# CH32V005F6P6.net
KiCad netlist of a schematic drawn in Altium Designer
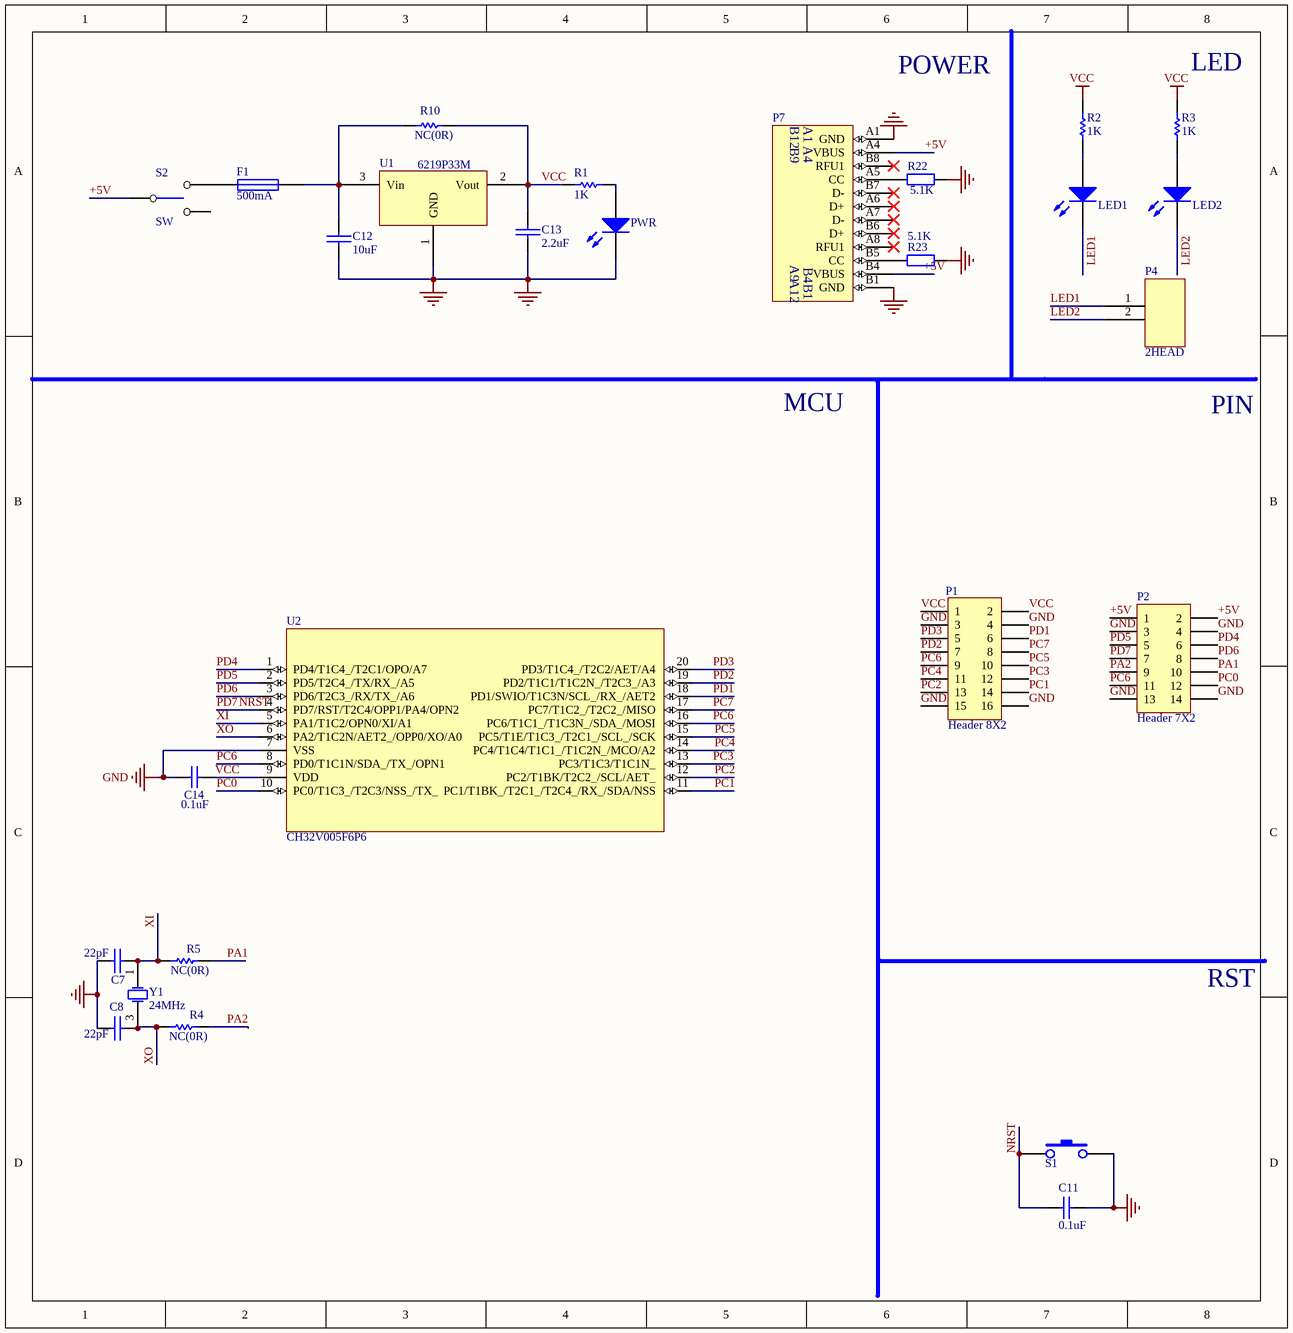
[diagram p0: CH32V005F6P6.SchDoc]

(export (version "E")
  (design (tool "Eeschema 10.0.6"))
  (components
    (comp (ref "C7")
      (value "22pF")
      (footprint "0402_C")
      (description "Capacitor")
      (libsource (lib "*") (part "CAP"))
    )
    (comp (ref "C8")
      (value "22pF")
      (footprint "0402_C")
      (description "Capacitor")
      (libsource (lib "*") (part "CAP"))
    )
    (comp (ref "C11")
      (value "0.1uF")
      (footprint "0603_C")
      (description "Capacitor")
      (fields (field (name "PUBLISHER") "Altium Limited"))
      (libsource (lib "*") (part "Cap"))
    )
    (comp (ref "C12")
      (value "10uF")
      (footprint "0603_C")
      (description "Capacitor")
      (libsource (lib "wch_sch_others") (part "CAP"))
    )
    (comp (ref "C13")
      (value "2.2uF")
      (footprint "0402_C")
      (description "Capacitor")
      (libsource (lib "wch_sch_others") (part "CAP"))
    )
    (comp (ref "C14")
      (value "0.1uF")
      (footprint "0603_C")
      (description "Capacitor")
      (fields (field (name "PUBLISHER") "Altium Limited"))
      (libsource (lib "*") (part "Cap"))
    )
    (comp (ref "F1")
      (value "500mA")
      (footprint "0603")
      (description "Fuse")
      (libsource (lib "*") (part "FUSE1"))
    )
    (comp (ref "LED1")
      (value "LED1   blue")
      (footprint "0603+")
      (description "Typical INFRARED GaAs LED")
      (fields (field (name "PUBLISHER") "Altium Limited"))
      (libsource (lib "*") (part "LED0"))
    )
    (comp (ref "LED2")
      (value "LED2  blue")
      (footprint "0603+")
      (description "Typical INFRARED GaAs LED")
      (fields (field (name "PUBLISHER") "Altium Limited"))
      (libsource (lib "*") (part "LED0"))
    )
    (comp (ref "P1")
      (value "Header 8X2")
      (footprint "HDR2X8")
      (description "Header, 8-Pin, Dual row")
      (fields (field (name "PUBLISHER") "Altium Limited"))
      (libsource (lib "Miscellaneous Connectors") (part "Header 8X2"))
    )
    (comp (ref "P2")
      (value "Header 7X2")
      (footprint "HDR2X7")
      (description "Header, 7-Pin, Dual row")
      (fields (field (name "PUBLISHER") "Altium Limited"))
      (libsource (lib "Miscellaneous Connectors") (part "Header 7X2"))
    )
    (comp (ref "P4") (value "2HEAD") (footprint "SIP2-2.54mm") (libsource (lib "*") (part "2HEAD")))
    (comp (ref "P7")
      (value "TYPE-C")
      (footprint "TYPE-C-Receptacle-2.0")
      (libsource (lib "*") (part "TYPE-C1"))
    )
    (comp (ref "PWR")
      (value "POWER  red")
      (footprint "0603+")
      (description "Typical INFRARED GaAs LED")
      (fields (field (name "PUBLISHER") "Altium Limited"))
      (libsource (lib "") (part "LED0_1"))
    )
    (comp (ref "R1")
      (value "1K")
      (footprint "0402")
      (description "Semiconductor Resistor")
      (fields (field (name "PUBLISHER") "Altium Limited"))
      (libsource (lib "*") (part "Res Semi"))
    )
    (comp (ref "R2")
      (value "1K")
      (footprint "0402")
      (description "Semiconductor Resistor")
      (fields (field (name "PUBLISHER") "Altium Limited"))
      (libsource (lib "*") (part "Res Semi"))
    )
    (comp (ref "R3")
      (value "1K")
      (footprint "0402")
      (description "Semiconductor Resistor")
      (fields (field (name "PUBLISHER") "Altium Limited"))
      (libsource (lib "*") (part "Res Semi"))
    )
    (comp (ref "R4")
      (value "NC(0R)")
      (footprint "0402")
      (description "Semiconductor Resistor")
      (fields (field (name "Comment") "0R") (field (name "PUBLISHER") "Altium Limited"))
      (libsource (lib "*") (part "Res Semi"))
    )
    (comp (ref "R5")
      (value "NC(0R)")
      (footprint "0402")
      (description "Semiconductor Resistor")
      (fields (field (name "Comment") "0R") (field (name "PUBLISHER") "Altium Limited"))
      (libsource (lib "*") (part "Res Semi"))
    )
    (comp (ref "R10")
      (value "NC(0R)")
      (footprint "0402")
      (description "Semiconductor Resistor")
      (fields (field (name "Comment") "0R") (field (name "PUBLISHER") "Altium Limited"))
      (libsource (lib "*") (part "Res Semi"))
    )
    (comp (ref "R22")
      (value "5.1K")
      (footprint "0402")
      (description "Resistor")
      (libsource (lib "Miscellaneous Devices") (part "Res2"))
    )
    (comp (ref "R23")
      (value "5.1K")
      (footprint "0402")
      (description "Resistor")
      (libsource (lib "Miscellaneous Devices") (part "Res2"))
    )
    (comp (ref "S1") (value "NRST") (footprint "SMD_6.1x3.65x2.5mm-KEY") (libsource (lib "*") (part "KEY")))
    (comp (ref "S2") (value "SW") (footprint "SW1") (libsource (lib "*") (part "SW")))
    (comp (ref "U1")
      (value "6219P33M")
      (footprint "SOT-23")
      (libsource (lib "wch_sch_others") (part "6219P33M"))
    )
    (comp (ref "U2")
      (value "CH32V005F6P6")
      (footprint "TSSOP20")
      (description "RISC-V MCU, 48MHz, ADC/OPA/2*UART/I2C/SPI")
      (libsource (lib "DHXXXSCH") (part "CH32V005F6P6"))
    )
    (comp (ref "Y1")
      (value "24MHz")
      (footprint "XT3225")
      (description "Crystal Oscillator")
      (fields (field (name "PUBLISHER") "Altium Limited"))
      (libsource (lib "*") (part "XTAL"))
    )
  )
  (nets
    (net (code "1") (name "/+5V") (class "Default")
      (node (ref "P2") (pin "1") (pinfunction "1_1") (pintype "passive"))
      (node (ref "P2") (pin "2") (pinfunction "2_2") (pintype "passive"))
      (node (ref "P7") (pin "A4") (pinfunction "VBUS_A4") (pintype "bidirectional"))
      (node (ref "P7") (pin "B4") (pinfunction "VBUS_B4") (pintype "bidirectional"))
      (node (ref "S2") (pin "1") (pinfunction "1_1") (pintype "passive"))
    )
    (net (code "2") (name "/LED1") (class "Default")
      (node (ref "LED1") (pin "2") (pinfunction "K_2") (pintype "passive"))
      (node (ref "P4") (pin "1") (pintype "passive"))
    )
    (net (code "3") (name "/LED2") (class "Default")
      (node (ref "LED2") (pin "2") (pinfunction "K_2") (pintype "passive"))
      (node (ref "P4") (pin "2") (pintype "passive"))
    )
    (net (code "4") (name "/NRST") (class "Default")
      (node (ref "C11") (pin "2") (pinfunction "2_2") (pintype "passive"))
      (node (ref "P2") (pin "7") (pinfunction "7_7") (pintype "passive"))
      (node (ref "S1") (pin "1") (pinfunction "1_1") (pintype "passive"))
      (node (ref "U2") (pin "4") (pinfunction "PD7/RST/T2C4/OPP1/PA4/OPN2_4") (pintype "bidirectional"))
    )
    (net (code "5") (name "/PA1") (class "Default")
      (node (ref "P2") (pin "10") (pinfunction "10_10") (pintype "passive"))
      (node (ref "R5") (pin "2") (pinfunction "2_2") (pintype "passive"))
    )
    (net (code "6") (name "/PA2") (class "Default")
      (node (ref "P2") (pin "9") (pinfunction "9_9") (pintype "passive"))
      (node (ref "R4") (pin "2") (pinfunction "2_2") (pintype "passive"))
    )
    (net (code "7") (name "/PC0") (class "Default")
      (node (ref "P2") (pin "12") (pinfunction "12_12") (pintype "passive"))
      (node (ref "U2") (pin "10") (pinfunction "PC0/T1C3_/T2C3/NSS_/TX__10") (pintype "bidirectional"))
    )
    (net (code "8") (name "/PC1") (class "Default")
      (node (ref "P1") (pin "14") (pinfunction "14_14") (pintype "passive"))
      (node (ref "U2") (pin "11") (pinfunction "PC1/T1BK_/T2C1_/T2C4_/RX_/SDA/NSS_11") (pintype "bidirectional"))
    )
    (net (code "9") (name "/PC2") (class "Default")
      (node (ref "P1") (pin "13") (pinfunction "13_13") (pintype "passive"))
      (node (ref "U2") (pin "12") (pinfunction "PC2/T1BK/T2C2_/SCL/AET__12") (pintype "bidirectional"))
    )
    (net (code "10") (name "/PC3") (class "Default")
      (node (ref "P1") (pin "12") (pinfunction "12_12") (pintype "passive"))
      (node (ref "U2") (pin "13") (pinfunction "PC3/T1C3/T1C1N__13") (pintype "bidirectional"))
    )
    (net (code "11") (name "/PC4") (class "Default")
      (node (ref "P1") (pin "11") (pinfunction "11_11") (pintype "passive"))
      (node (ref "U2") (pin "14") (pinfunction "PC4/T1C4/T1C1_/T1C2N_/MCO/A2_14") (pintype "bidirectional"))
    )
    (net (code "12") (name "/PC5") (class "Default")
      (node (ref "P1") (pin "10") (pinfunction "10_10") (pintype "passive"))
      (node (ref "U2") (pin "15") (pinfunction "PC5/T1E/T1C3_/T2C1_/SCL_/SCK_15") (pintype "bidirectional"))
    )
    (net (code "13") (name "/PC6") (class "Default")
      (node (ref "P1") (pin "9") (pinfunction "9_9") (pintype "passive"))
      (node (ref "P2") (pin "11") (pinfunction "11_11") (pintype "passive"))
      (node (ref "U2") (pin "16") (pinfunction "PC6/T1C1_/T1C3N_/SDA_/MOSI_16") (pintype "bidirectional"))
      (node (ref "U2") (pin "8") (pinfunction "PD0/T1C1N/SDA_/TX_/OPN1_8") (pintype "bidirectional"))
    )
    (net (code "14") (name "/PC7") (class "Default")
      (node (ref "P1") (pin "8") (pinfunction "8_8") (pintype "passive"))
      (node (ref "U2") (pin "17") (pinfunction "PC7/T1C2_/T2C2_/MISO_17") (pintype "bidirectional"))
    )
    (net (code "15") (name "/PD1") (class "Default")
      (node (ref "P1") (pin "6") (pinfunction "6_6") (pintype "passive"))
      (node (ref "U2") (pin "18") (pinfunction "PD1/SWIO/T1C3N/SCL_/RX_/AET2_18") (pintype "bidirectional"))
    )
    (net (code "16") (name "/PD2") (class "Default")
      (node (ref "P1") (pin "7") (pinfunction "7_7") (pintype "passive"))
      (node (ref "U2") (pin "19") (pinfunction "PD2/T1C1/T1C2N_/T2C3_/A3_19") (pintype "bidirectional"))
    )
    (net (code "17") (name "/PD3") (class "Default")
      (node (ref "P1") (pin "5") (pinfunction "5_5") (pintype "passive"))
      (node (ref "U2") (pin "20") (pinfunction "PD3/T1C4_/T2C2/AET/A4_20") (pintype "bidirectional"))
    )
    (net (code "18") (name "/PD4") (class "Default")
      (node (ref "P2") (pin "6") (pinfunction "6_6") (pintype "passive"))
      (node (ref "U2") (pin "1") (pinfunction "PD4/T1C4_/T2C1/OPO/A7_1") (pintype "bidirectional"))
    )
    (net (code "19") (name "/PD5") (class "Default")
      (node (ref "P2") (pin "5") (pinfunction "5_5") (pintype "passive"))
      (node (ref "U2") (pin "2") (pinfunction "PD5/T2C4_/TX/RX_/A5_2") (pintype "bidirectional"))
    )
    (net (code "20") (name "/PD6") (class "Default")
      (node (ref "P2") (pin "8") (pinfunction "8_8") (pintype "passive"))
      (node (ref "U2") (pin "3") (pinfunction "PD6/T2C3_/RX/TX_/A6_3") (pintype "bidirectional"))
    )
    (net (code "21") (name "/XI") (class "Default")
      (node (ref "C7") (pin "2") (pinfunction "2_2") (pintype "passive"))
      (node (ref "R5") (pin "1") (pinfunction "1_1") (pintype "passive"))
      (node (ref "U2") (pin "5") (pinfunction "PA1/T1C2/OPN0/XI/A1_5") (pintype "bidirectional"))
      (node (ref "Y1") (pin "1") (pinfunction "OSC1_1") (pintype "passive"))
    )
    (net (code "22") (name "/XO") (class "Default")
      (node (ref "C8") (pin "2") (pinfunction "2_2") (pintype "passive"))
      (node (ref "R4") (pin "1") (pinfunction "1_1") (pintype "passive"))
      (node (ref "U2") (pin "6") (pinfunction "PA2/T1C2N/AET2_/OPP0/XO/A0_6") (pintype "bidirectional"))
      (node (ref "Y1") (pin "3") (pinfunction "OSC2_3") (pintype "passive"))
    )
    (net (code "23") (name "GND") (class "Default")
      (node (ref "C11") (pin "1") (pinfunction "1_1") (pintype "passive"))
      (node (ref "C12") (pin "2") (pinfunction "2_2") (pintype "passive"))
      (node (ref "C13") (pin "1") (pinfunction "1_1") (pintype "passive"))
      (node (ref "C14") (pin "2") (pinfunction "2_2") (pintype "passive"))
      (node (ref "C7") (pin "1") (pinfunction "1_1") (pintype "passive"))
      (node (ref "C8") (pin "1") (pinfunction "1_1") (pintype "passive"))
      (node (ref "P1") (pin "15") (pinfunction "15_15") (pintype "passive"))
      (node (ref "P1") (pin "16") (pinfunction "16_16") (pintype "passive"))
      (node (ref "P1") (pin "3") (pinfunction "3_3") (pintype "passive"))
      (node (ref "P1") (pin "4") (pinfunction "4_4") (pintype "passive"))
      (node (ref "P2") (pin "13") (pinfunction "13_13") (pintype "passive"))
      (node (ref "P2") (pin "14") (pinfunction "14_14") (pintype "passive"))
      (node (ref "P2") (pin "3") (pinfunction "3_3") (pintype "passive"))
      (node (ref "P2") (pin "4") (pinfunction "4_4") (pintype "passive"))
      (node (ref "P7") (pin "A1") (pinfunction "GND_A1") (pintype "bidirectional"))
      (node (ref "P7") (pin "B1") (pinfunction "GND_B1") (pintype "bidirectional"))
      (node (ref "PWR") (pin "2") (pinfunction "K_2") (pintype "passive"))
      (node (ref "R22") (pin "2") (pinfunction "2_2") (pintype "passive"))
      (node (ref "R23") (pin "2") (pinfunction "2_2") (pintype "passive"))
      (node (ref "S1") (pin "2") (pinfunction "2_2") (pintype "passive"))
      (node (ref "U1") (pin "1") (pinfunction "GND_1") (pintype "passive"))
      (node (ref "U2") (pin "7") (pinfunction "VSS_7") (pintype "power_in"))
    )
    (net (code "24") (name "Net-(F1-Pad1)") (class "Default")
      (node (ref "F1") (pin "1") (pinfunction "1_1") (pintype "passive"))
      (node (ref "S2") (pin "3") (pinfunction "3_3") (pintype "passive"))
    )
    (net (code "25") (name "Net-(LED1-A)") (class "Default")
      (node (ref "LED1") (pin "1") (pinfunction "A_1") (pintype "passive"))
      (node (ref "R2") (pin "2") (pinfunction "2_2") (pintype "passive"))
    )
    (net (code "26") (name "Net-(LED2-A)") (class "Default")
      (node (ref "LED2") (pin "1") (pinfunction "A_1") (pintype "passive"))
      (node (ref "R3") (pin "2") (pinfunction "2_2") (pintype "passive"))
    )
    (net (code "27") (name "Net-(P7-CC-PadA5)") (class "Default")
      (node (ref "P7") (pin "A5") (pinfunction "CC_A5") (pintype "bidirectional"))
      (node (ref "R22") (pin "1") (pinfunction "1_1") (pintype "passive"))
    )
    (net (code "28") (name "Net-(P7-CC-PadB5)") (class "Default")
      (node (ref "P7") (pin "B5") (pinfunction "CC_B5") (pintype "bidirectional"))
      (node (ref "R23") (pin "1") (pinfunction "1_1") (pintype "passive"))
    )
    (net (code "29") (name "Net-(PWR-A)") (class "Default")
      (node (ref "PWR") (pin "1") (pinfunction "A_1") (pintype "passive"))
      (node (ref "R1") (pin "1") (pinfunction "1_1") (pintype "passive"))
    )
    (net (code "30") (name "Net-(U1-Vin)") (class "Default")
      (node (ref "C12") (pin "1") (pinfunction "1_1") (pintype "passive"))
      (node (ref "F1") (pin "2") (pinfunction "2_2") (pintype "passive"))
      (node (ref "R10") (pin "1") (pinfunction "1_1") (pintype "passive"))
      (node (ref "U1") (pin "3") (pinfunction "Vin_3") (pintype "passive"))
    )
    (net (code "31") (name "VCC") (class "Default")
      (node (ref "C13") (pin "2") (pinfunction "2_2") (pintype "passive"))
      (node (ref "C14") (pin "1") (pinfunction "1_1") (pintype "passive"))
      (node (ref "P1") (pin "1") (pinfunction "1_1") (pintype "passive"))
      (node (ref "P1") (pin "2") (pinfunction "2_2") (pintype "passive"))
      (node (ref "R1") (pin "2") (pinfunction "2_2") (pintype "passive"))
      (node (ref "R10") (pin "2") (pinfunction "2_2") (pintype "passive"))
      (node (ref "R2") (pin "1") (pinfunction "1_1") (pintype "passive"))
      (node (ref "R3") (pin "1") (pinfunction "1_1") (pintype "passive"))
      (node (ref "U1") (pin "2") (pinfunction "Vout_2") (pintype "passive"))
      (node (ref "U2") (pin "9") (pinfunction "VDD_9") (pintype "power_in"))
    )
    (net (code "32") (name "unconnected-(P7-D+-PadA6)") (class "Default")
      (node (ref "P7") (pin "A6") (pinfunction "D+_A6") (pintype "bidirectional+no_connect"))
    )
    (net (code "33") (name "unconnected-(P7-D+-PadB6)") (class "Default")
      (node (ref "P7") (pin "B6") (pinfunction "D+_B6") (pintype "bidirectional+no_connect"))
    )
    (net (code "34") (name "unconnected-(P7-D--PadA7)") (class "Default")
      (node (ref "P7") (pin "A7") (pinfunction "D-_A7") (pintype "bidirectional+no_connect"))
    )
    (net (code "35") (name "unconnected-(P7-D--PadB7)") (class "Default")
      (node (ref "P7") (pin "B7") (pinfunction "D-_B7") (pintype "bidirectional+no_connect"))
    )
    (net (code "36") (name "unconnected-(P7-RFU1-PadA8)") (class "Default")
      (node (ref "P7") (pin "A8") (pinfunction "RFU1_A8") (pintype "bidirectional+no_connect"))
    )
    (net (code "37") (name "unconnected-(P7-RFU1-PadB8)") (class "Default")
      (node (ref "P7") (pin "B8") (pinfunction "RFU1_B8") (pintype "bidirectional+no_connect"))
    )
    (net (code "38") (name "unconnected-(S2-Pad2)") (class "Default")
      (node (ref "S2") (pin "2") (pinfunction "2_2") (pintype "passive"))
    )
  )
)
